# main.net
KiCad netlist of a schematic drawn in Altium Designer
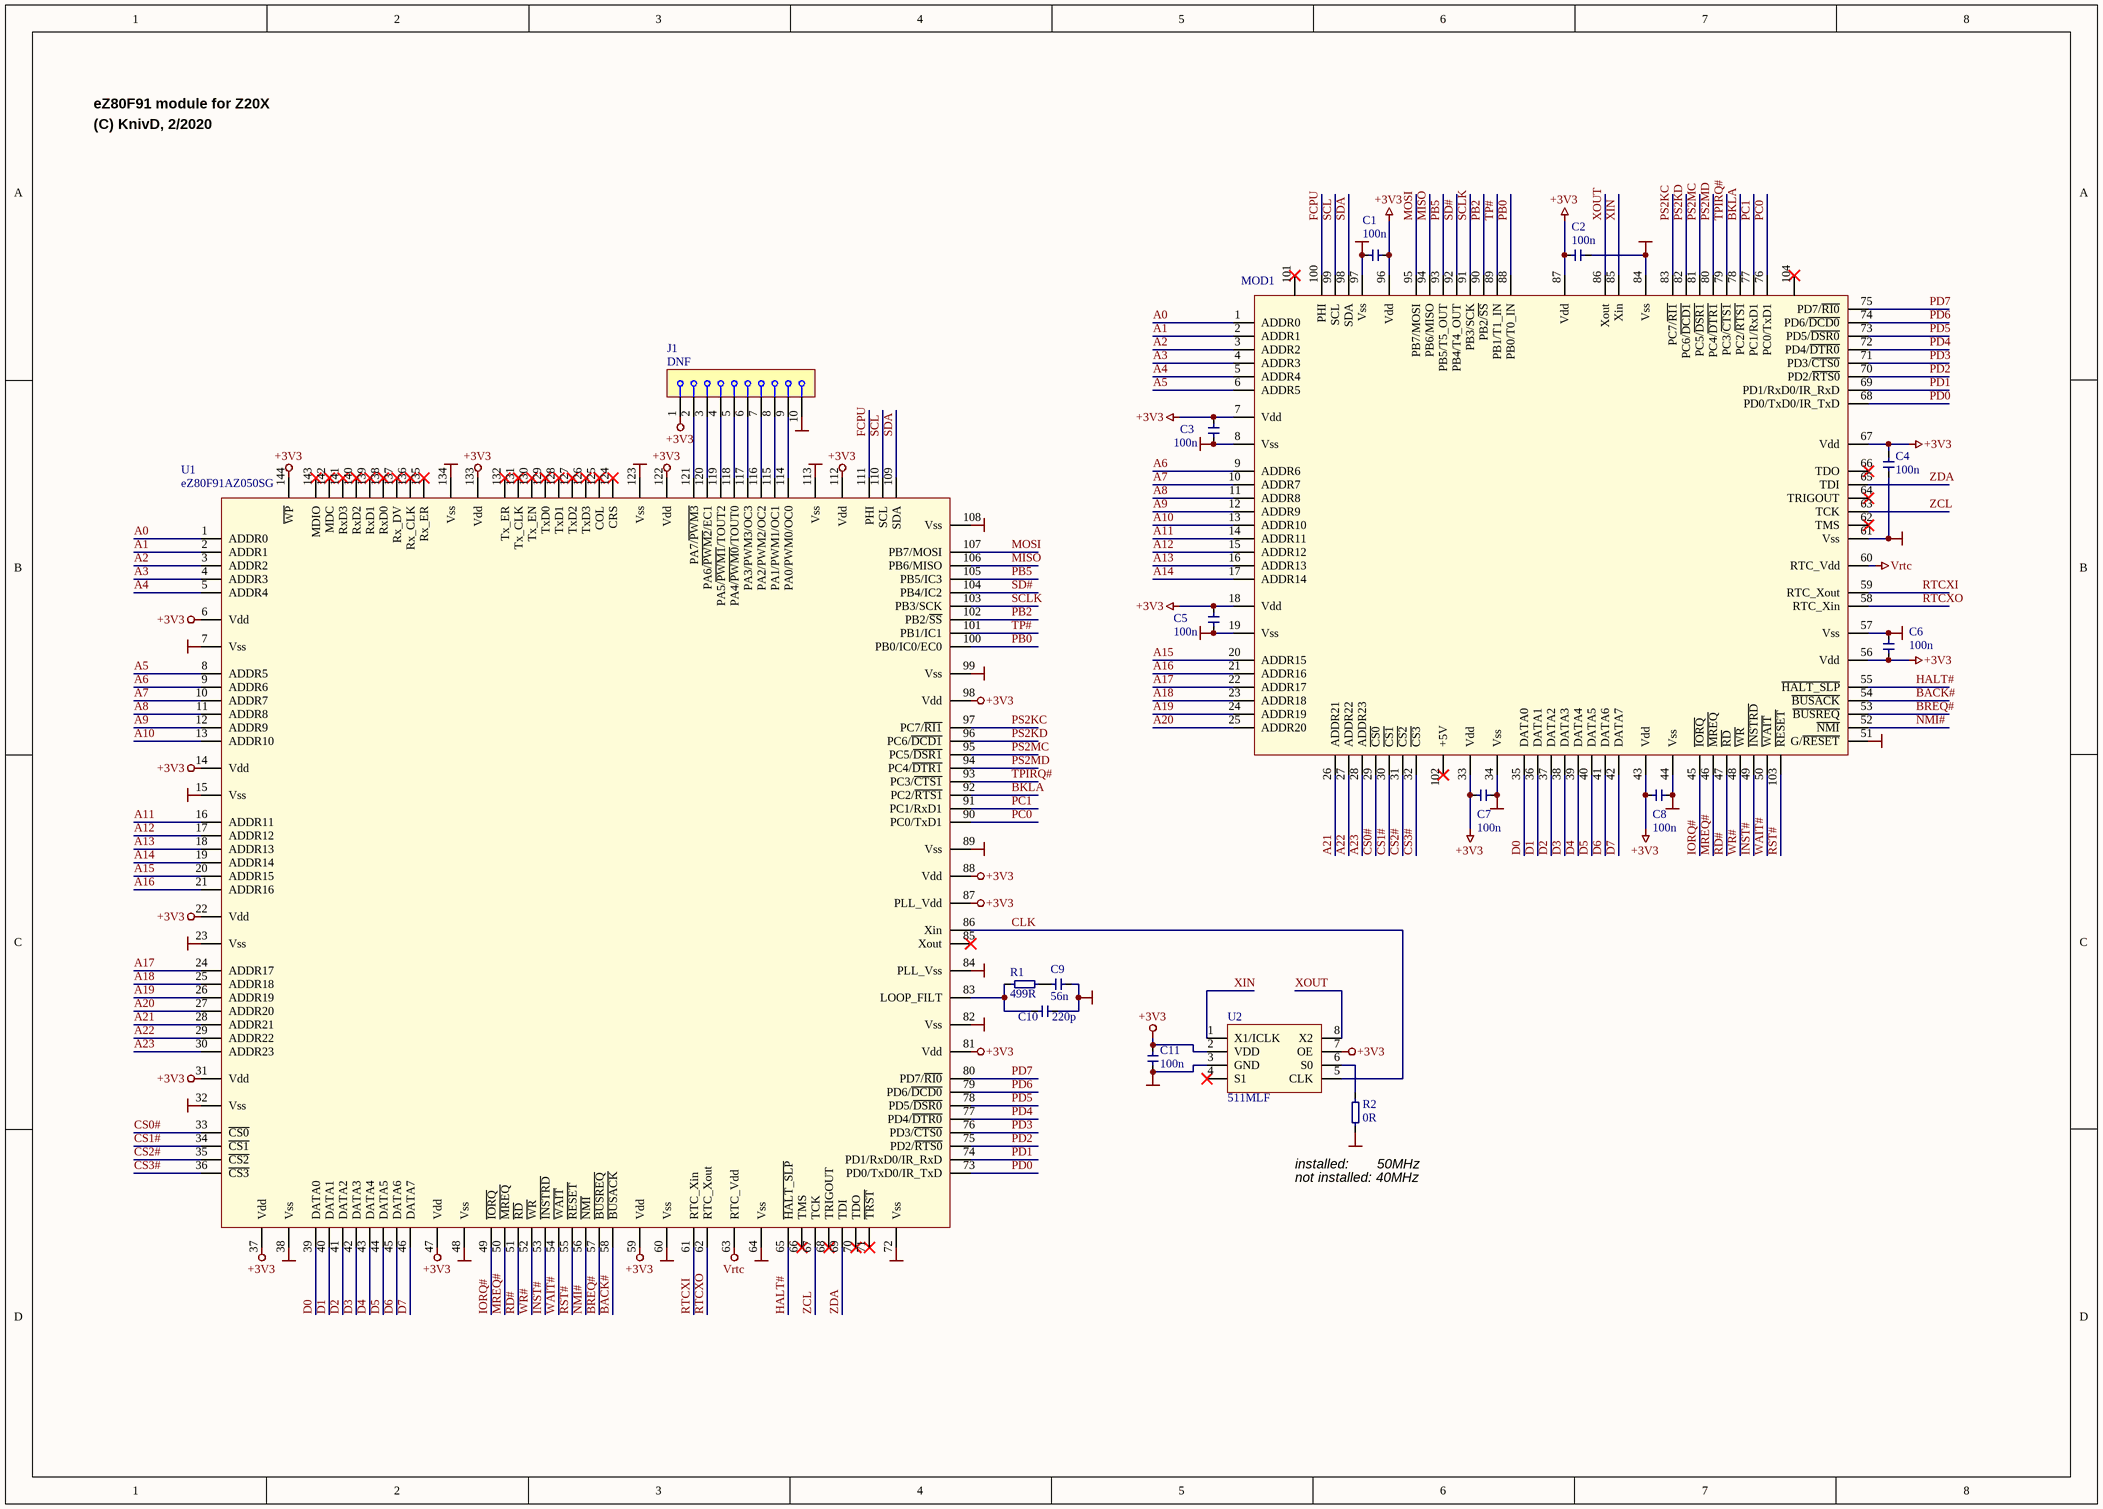
[diagram p0: main.SchDoc]

(export (version "E")
  (design (tool "Eeschema 10.0.6"))
  (components
    (comp (ref "C1")
      (value "100n")
      (footprint "_0805_CAP")
      (description "Capacitor")
      (libsource (lib "Discretes") (part "Capacitor"))
    )
    (comp (ref "C2")
      (value "100n")
      (footprint "_0805_CAP")
      (description "Capacitor")
      (libsource (lib "Discretes") (part "Capacitor"))
    )
    (comp (ref "C3")
      (value "100n")
      (footprint "_0805_CAP")
      (description "Capacitor")
      (libsource (lib "Discretes") (part "Capacitor"))
    )
    (comp (ref "C4")
      (value "100n")
      (footprint "_0805_CAP")
      (description "Capacitor")
      (libsource (lib "Discretes") (part "Capacitor"))
    )
    (comp (ref "C5")
      (value "100n")
      (footprint "_0805_CAP")
      (description "Capacitor")
      (libsource (lib "Discretes") (part "Capacitor"))
    )
    (comp (ref "C6")
      (value "100n")
      (footprint "_0805_CAP")
      (description "Capacitor")
      (libsource (lib "Discretes") (part "Capacitor"))
    )
    (comp (ref "C7")
      (value "100n")
      (footprint "_0805_CAP")
      (description "Capacitor")
      (libsource (lib "Discretes") (part "Capacitor"))
    )
    (comp (ref "C8")
      (value "100n")
      (footprint "_0805_CAP")
      (description "Capacitor")
      (libsource (lib "Discretes") (part "Capacitor"))
    )
    (comp (ref "C9")
      (value "56n")
      (footprint "_0805_CAP")
      (description "Capacitor")
      (libsource (lib "Discretes") (part "Capacitor"))
    )
    (comp (ref "C10")
      (value "220p")
      (footprint "_0805_CAP")
      (description "Capacitor")
      (libsource (lib "Discretes") (part "Capacitor"))
    )
    (comp (ref "C11")
      (value "100n")
      (footprint "_0805_CAP")
      (description "Capacitor")
      (libsource (lib "Discretes") (part "Capacitor"))
    )
    (comp (ref "J1")
      (value "DNF")
      (footprint "2011-1X10S")
      (description "Single row, 10-way connector")
      (libsource (lib "Connectors") (part "Connector 1x10"))
    )
    (comp (ref "MOD1")
      (value "Z20X CPU Module")
      (footprint "PGA100X15")
      (libsource (lib "Modules") (part "Z20X CPU Module"))
    )
    (comp (ref "R1")
      (value "499R")
      (footprint "_0805_RES")
      (description "Resistor")
      (libsource (lib "Discretes") (part "Resistor"))
    )
    (comp (ref "R2")
      (value "0R")
      (footprint "_0805_RES")
      (description "Resistor")
      (libsource (lib "") (part "Resistor_1"))
    )
    (comp (ref "U1")
      (value "eZ80F91AZ050SG")
      (footprint "QFP50P2200X2200X160-144N")
      (description "eZ80Acclaim!® Flash Microcontrollers")
      (fields (field (name "MANUFACTURER") "Zilog"))
      (libsource (lib "IC Microcontrollers and Processors") (part "eZ80F91"))
    )
    (comp (ref "U2")
      (value "511MLF")
      (footprint "SOIC8")
      (description "LOCO(tm) PLL CLOCK MULTIPLIER")
      (libsource (lib "IC Other Functions") (part "ICS511"))
    )
  )
  (nets
    (net (code "1") (name "+3V3") (class "Default")
      (node (ref "C1") (pin "1") (pintype "passive"))
      (node (ref "C11") (pin "2") (pintype "passive"))
      (node (ref "C2") (pin "2") (pintype "passive"))
      (node (ref "C3") (pin "1") (pintype "passive"))
      (node (ref "C4") (pin "2") (pintype "passive"))
      (node (ref "C5") (pin "1") (pintype "passive"))
      (node (ref "C6") (pin "1") (pintype "passive"))
      (node (ref "C7") (pin "1") (pintype "passive"))
      (node (ref "C8") (pin "1") (pintype "passive"))
      (node (ref "J1") (pin "1") (pinfunction "1_1") (pintype "passive"))
      (node (ref "MOD1") (pin "18") (pinfunction "Vdd_18") (pintype "passive"))
      (node (ref "MOD1") (pin "33") (pinfunction "Vdd_33") (pintype "passive"))
      (node (ref "MOD1") (pin "43") (pinfunction "Vdd_43") (pintype "passive"))
      (node (ref "MOD1") (pin "56") (pinfunction "Vdd_56") (pintype "passive"))
      (node (ref "MOD1") (pin "67") (pinfunction "Vdd_67") (pintype "passive"))
      (node (ref "MOD1") (pin "7") (pinfunction "Vdd_7") (pintype "passive"))
      (node (ref "MOD1") (pin "87") (pinfunction "Vdd_87") (pintype "passive"))
      (node (ref "MOD1") (pin "96") (pinfunction "Vdd_96") (pintype "passive"))
      (node (ref "U1") (pin "112") (pinfunction "Vdd_112") (pintype "passive"))
      (node (ref "U1") (pin "122") (pinfunction "Vdd_122") (pintype "passive"))
      (node (ref "U1") (pin "133") (pinfunction "Vdd_133") (pintype "passive"))
      (node (ref "U1") (pin "14") (pinfunction "Vdd_14") (pintype "passive"))
      (node (ref "U1") (pin "144") (pinfunction "~{WP}_144") (pintype "passive"))
      (node (ref "U1") (pin "22") (pinfunction "Vdd_22") (pintype "passive"))
      (node (ref "U1") (pin "31") (pinfunction "Vdd_31") (pintype "passive"))
      (node (ref "U1") (pin "37") (pinfunction "Vdd_37") (pintype "passive"))
      (node (ref "U1") (pin "47") (pinfunction "Vdd_47") (pintype "passive"))
      (node (ref "U1") (pin "59") (pinfunction "Vdd_59") (pintype "passive"))
      (node (ref "U1") (pin "6") (pinfunction "Vdd_6") (pintype "passive"))
      (node (ref "U1") (pin "81") (pinfunction "Vdd_81") (pintype "passive"))
      (node (ref "U1") (pin "87") (pinfunction "PLL_Vdd_87") (pintype "passive"))
      (node (ref "U1") (pin "88") (pinfunction "Vdd_88") (pintype "passive"))
      (node (ref "U1") (pin "98") (pinfunction "Vdd_98") (pintype "passive"))
      (node (ref "U2") (pin "2") (pinfunction "VDD_2") (pintype "passive"))
      (node (ref "U2") (pin "7") (pinfunction "OE_7") (pintype "passive"))
    )
    (net (code "2") (name "/A0") (class "Default")
      (node (ref "MOD1") (pin "1") (pinfunction "ADDR0_1") (pintype "passive"))
      (node (ref "U1") (pin "1") (pinfunction "ADDR0_1") (pintype "passive"))
    )
    (net (code "3") (name "/A1") (class "Default")
      (node (ref "MOD1") (pin "2") (pinfunction "ADDR1_2") (pintype "passive"))
      (node (ref "U1") (pin "2") (pinfunction "ADDR1_2") (pintype "passive"))
    )
    (net (code "4") (name "/A2") (class "Default")
      (node (ref "MOD1") (pin "3") (pinfunction "ADDR2_3") (pintype "passive"))
      (node (ref "U1") (pin "3") (pinfunction "ADDR2_3") (pintype "passive"))
    )
    (net (code "5") (name "/A3") (class "Default")
      (node (ref "MOD1") (pin "4") (pinfunction "ADDR3_4") (pintype "passive"))
      (node (ref "U1") (pin "4") (pinfunction "ADDR3_4") (pintype "passive"))
    )
    (net (code "6") (name "/A4") (class "Default")
      (node (ref "MOD1") (pin "5") (pinfunction "ADDR4_5") (pintype "passive"))
      (node (ref "U1") (pin "5") (pinfunction "ADDR4_5") (pintype "passive"))
    )
    (net (code "7") (name "/A5") (class "Default")
      (node (ref "MOD1") (pin "6") (pinfunction "ADDR5_6") (pintype "passive"))
      (node (ref "U1") (pin "8") (pinfunction "ADDR5_8") (pintype "passive"))
    )
    (net (code "8") (name "/A6") (class "Default")
      (node (ref "MOD1") (pin "9") (pinfunction "ADDR6_9") (pintype "passive"))
      (node (ref "U1") (pin "9") (pinfunction "ADDR6_9") (pintype "passive"))
    )
    (net (code "9") (name "/A7") (class "Default")
      (node (ref "MOD1") (pin "10") (pinfunction "ADDR7_10") (pintype "passive"))
      (node (ref "U1") (pin "10") (pinfunction "ADDR7_10") (pintype "passive"))
    )
    (net (code "10") (name "/A8") (class "Default")
      (node (ref "MOD1") (pin "11") (pinfunction "ADDR8_11") (pintype "passive"))
      (node (ref "U1") (pin "11") (pinfunction "ADDR8_11") (pintype "passive"))
    )
    (net (code "11") (name "/A9") (class "Default")
      (node (ref "MOD1") (pin "12") (pinfunction "ADDR9_12") (pintype "passive"))
      (node (ref "U1") (pin "12") (pinfunction "ADDR9_12") (pintype "passive"))
    )
    (net (code "12") (name "/A10") (class "Default")
      (node (ref "MOD1") (pin "13") (pinfunction "ADDR10_13") (pintype "passive"))
      (node (ref "U1") (pin "13") (pinfunction "ADDR10_13") (pintype "passive"))
    )
    (net (code "13") (name "/A11") (class "Default")
      (node (ref "MOD1") (pin "14") (pinfunction "ADDR11_14") (pintype "passive"))
      (node (ref "U1") (pin "16") (pinfunction "ADDR11_16") (pintype "passive"))
    )
    (net (code "14") (name "/A12") (class "Default")
      (node (ref "MOD1") (pin "15") (pinfunction "ADDR12_15") (pintype "passive"))
      (node (ref "U1") (pin "17") (pinfunction "ADDR12_17") (pintype "passive"))
    )
    (net (code "15") (name "/A13") (class "Default")
      (node (ref "MOD1") (pin "16") (pinfunction "ADDR13_16") (pintype "passive"))
      (node (ref "U1") (pin "18") (pinfunction "ADDR13_18") (pintype "passive"))
    )
    (net (code "16") (name "/A14") (class "Default")
      (node (ref "MOD1") (pin "17") (pinfunction "ADDR14_17") (pintype "passive"))
      (node (ref "U1") (pin "19") (pinfunction "ADDR14_19") (pintype "passive"))
    )
    (net (code "17") (name "/A15") (class "Default")
      (node (ref "MOD1") (pin "20") (pinfunction "ADDR15_20") (pintype "passive"))
      (node (ref "U1") (pin "20") (pinfunction "ADDR15_20") (pintype "passive"))
    )
    (net (code "18") (name "/A16") (class "Default")
      (node (ref "MOD1") (pin "21") (pinfunction "ADDR16_21") (pintype "passive"))
      (node (ref "U1") (pin "21") (pinfunction "ADDR16_21") (pintype "passive"))
    )
    (net (code "19") (name "/A17") (class "Default")
      (node (ref "MOD1") (pin "22") (pinfunction "ADDR17_22") (pintype "passive"))
      (node (ref "U1") (pin "24") (pinfunction "ADDR17_24") (pintype "passive"))
    )
    (net (code "20") (name "/A18") (class "Default")
      (node (ref "MOD1") (pin "23") (pinfunction "ADDR18_23") (pintype "passive"))
      (node (ref "U1") (pin "25") (pinfunction "ADDR18_25") (pintype "passive"))
    )
    (net (code "21") (name "/A19") (class "Default")
      (node (ref "MOD1") (pin "24") (pinfunction "ADDR19_24") (pintype "passive"))
      (node (ref "U1") (pin "26") (pinfunction "ADDR19_26") (pintype "passive"))
    )
    (net (code "22") (name "/A20") (class "Default")
      (node (ref "MOD1") (pin "25") (pinfunction "ADDR20_25") (pintype "passive"))
      (node (ref "U1") (pin "27") (pinfunction "ADDR20_27") (pintype "passive"))
    )
    (net (code "23") (name "/A21") (class "Default")
      (node (ref "MOD1") (pin "26") (pinfunction "ADDR21_26") (pintype "passive"))
      (node (ref "U1") (pin "28") (pinfunction "ADDR21_28") (pintype "passive"))
    )
    (net (code "24") (name "/A22") (class "Default")
      (node (ref "MOD1") (pin "27") (pinfunction "ADDR22_27") (pintype "passive"))
      (node (ref "U1") (pin "29") (pinfunction "ADDR22_29") (pintype "passive"))
    )
    (net (code "25") (name "/A23") (class "Default")
      (node (ref "MOD1") (pin "28") (pinfunction "ADDR23_28") (pintype "passive"))
      (node (ref "U1") (pin "30") (pinfunction "ADDR23_30") (pintype "passive"))
    )
    (net (code "26") (name "/BACK#") (class "Default")
      (node (ref "MOD1") (pin "54") (pinfunction "~{BUSACK}_54") (pintype "passive"))
      (node (ref "U1") (pin "58") (pinfunction "~{BUSACK}_58") (pintype "passive"))
    )
    (net (code "27") (name "/BKLA") (class "Default")
      (node (ref "MOD1") (pin "78") (pinfunction "PC2/~{RTS1}_78") (pintype "passive"))
      (node (ref "U1") (pin "92") (pinfunction "PC2/~{RTS1}_92") (pintype "passive"))
    )
    (net (code "28") (name "/BREQ#") (class "Default")
      (node (ref "MOD1") (pin "53") (pinfunction "~{BUSREQ}_53") (pintype "passive"))
      (node (ref "U1") (pin "57") (pinfunction "~{BUSREQ}_57") (pintype "passive"))
    )
    (net (code "29") (name "/CLK") (class "Default")
      (node (ref "U1") (pin "86") (pinfunction "Xin_86") (pintype "passive"))
      (node (ref "U2") (pin "5") (pinfunction "CLK_5") (pintype "passive"))
    )
    (net (code "30") (name "/CS0#") (class "Default")
      (node (ref "MOD1") (pin "29") (pinfunction "~{CS0}_29") (pintype "passive"))
      (node (ref "U1") (pin "33") (pinfunction "~{CS0}_33") (pintype "passive"))
    )
    (net (code "31") (name "/CS1#") (class "Default")
      (node (ref "MOD1") (pin "30") (pinfunction "~{CS1}_30") (pintype "passive"))
      (node (ref "U1") (pin "34") (pinfunction "~{CS1}_34") (pintype "passive"))
    )
    (net (code "32") (name "/CS2#") (class "Default")
      (node (ref "MOD1") (pin "31") (pinfunction "~{CS2}_31") (pintype "passive"))
      (node (ref "U1") (pin "35") (pinfunction "~{CS2}_35") (pintype "passive"))
    )
    (net (code "33") (name "/CS3#") (class "Default")
      (node (ref "MOD1") (pin "32") (pinfunction "~{CS3}_32") (pintype "passive"))
      (node (ref "U1") (pin "36") (pinfunction "~{CS3}_36") (pintype "passive"))
    )
    (net (code "34") (name "/D0") (class "Default")
      (node (ref "MOD1") (pin "35") (pinfunction "DATA0_35") (pintype "passive"))
      (node (ref "U1") (pin "39") (pinfunction "DATA0_39") (pintype "passive"))
    )
    (net (code "35") (name "/D1") (class "Default")
      (node (ref "MOD1") (pin "36") (pinfunction "DATA1_36") (pintype "passive"))
      (node (ref "U1") (pin "40") (pinfunction "DATA1_40") (pintype "passive"))
    )
    (net (code "36") (name "/D2") (class "Default")
      (node (ref "MOD1") (pin "37") (pinfunction "DATA2_37") (pintype "passive"))
      (node (ref "U1") (pin "41") (pinfunction "DATA2_41") (pintype "passive"))
    )
    (net (code "37") (name "/D3") (class "Default")
      (node (ref "MOD1") (pin "38") (pinfunction "DATA3_38") (pintype "passive"))
      (node (ref "U1") (pin "42") (pinfunction "DATA3_42") (pintype "passive"))
    )
    (net (code "38") (name "/D4") (class "Default")
      (node (ref "MOD1") (pin "39") (pinfunction "DATA4_39") (pintype "passive"))
      (node (ref "U1") (pin "43") (pinfunction "DATA4_43") (pintype "passive"))
    )
    (net (code "39") (name "/D5") (class "Default")
      (node (ref "MOD1") (pin "40") (pinfunction "DATA5_40") (pintype "passive"))
      (node (ref "U1") (pin "44") (pinfunction "DATA5_44") (pintype "passive"))
    )
    (net (code "40") (name "/D6") (class "Default")
      (node (ref "MOD1") (pin "41") (pinfunction "DATA6_41") (pintype "passive"))
      (node (ref "U1") (pin "45") (pinfunction "DATA6_45") (pintype "passive"))
    )
    (net (code "41") (name "/D7") (class "Default")
      (node (ref "MOD1") (pin "42") (pinfunction "DATA7_42") (pintype "passive"))
      (node (ref "U1") (pin "46") (pinfunction "DATA7_46") (pintype "passive"))
    )
    (net (code "42") (name "/FCPU") (class "Default")
      (node (ref "MOD1") (pin "100") (pinfunction "PHI_100") (pintype "passive"))
      (node (ref "U1") (pin "111") (pinfunction "PHI_111") (pintype "passive"))
    )
    (net (code "43") (name "/HALT#") (class "Default")
      (node (ref "MOD1") (pin "55") (pinfunction "~{HALT_SLP}_55") (pintype "passive"))
      (node (ref "U1") (pin "65") (pinfunction "~{HALT_SLP}_65") (pintype "passive"))
    )
    (net (code "44") (name "/INST#") (class "Default")
      (node (ref "MOD1") (pin "49") (pinfunction "~{INSTRD}_49") (pintype "passive"))
      (node (ref "U1") (pin "53") (pinfunction "~{INSTRD}_53") (pintype "passive"))
    )
    (net (code "45") (name "/IORQ#") (class "Default")
      (node (ref "MOD1") (pin "45") (pinfunction "~{IORQ}_45") (pintype "passive"))
      (node (ref "U1") (pin "49") (pinfunction "~{IORQ}_49") (pintype "passive"))
    )
    (net (code "46") (name "/MISO") (class "Default")
      (node (ref "MOD1") (pin "94") (pinfunction "PB6/MISO_94") (pintype "passive"))
      (node (ref "U1") (pin "106") (pinfunction "PB6/MISO_106") (pintype "passive"))
    )
    (net (code "47") (name "/MOSI") (class "Default")
      (node (ref "MOD1") (pin "95") (pinfunction "PB7/MOSI_95") (pintype "passive"))
      (node (ref "U1") (pin "107") (pinfunction "PB7/MOSI_107") (pintype "passive"))
    )
    (net (code "48") (name "/MREQ#") (class "Default")
      (node (ref "MOD1") (pin "46") (pinfunction "~{MREQ}_46") (pintype "passive"))
      (node (ref "U1") (pin "50") (pinfunction "~{MREQ}_50") (pintype "passive"))
    )
    (net (code "49") (name "/NMI#") (class "Default")
      (node (ref "MOD1") (pin "52") (pinfunction "~{NMI}_52") (pintype "passive"))
      (node (ref "U1") (pin "56") (pinfunction "~{NMI}_56") (pintype "passive"))
    )
    (net (code "50") (name "/PB0") (class "Default")
      (node (ref "MOD1") (pin "88") (pinfunction "PB0/T0_IN_88") (pintype "passive"))
      (node (ref "U1") (pin "100") (pinfunction "PB0/IC0/EC0_100") (pintype "passive"))
    )
    (net (code "51") (name "/PB2") (class "Default")
      (node (ref "MOD1") (pin "90") (pinfunction "PB2/~{SS}_90") (pintype "passive"))
      (node (ref "U1") (pin "102") (pinfunction "PB2/~{SS}_102") (pintype "passive"))
    )
    (net (code "52") (name "/PB5") (class "Default")
      (node (ref "MOD1") (pin "93") (pinfunction "PB5/T5_OUT_93") (pintype "passive"))
      (node (ref "U1") (pin "105") (pinfunction "PB5/IC3_105") (pintype "passive"))
    )
    (net (code "53") (name "/PC0") (class "Default")
      (node (ref "MOD1") (pin "76") (pinfunction "PC0/TxD1_76") (pintype "passive"))
      (node (ref "U1") (pin "90") (pinfunction "PC0/TxD1_90") (pintype "passive"))
    )
    (net (code "54") (name "/PC1") (class "Default")
      (node (ref "MOD1") (pin "77") (pinfunction "PC1/RxD1_77") (pintype "passive"))
      (node (ref "U1") (pin "91") (pinfunction "PC1/RxD1_91") (pintype "passive"))
    )
    (net (code "55") (name "/PD0") (class "Default")
      (node (ref "MOD1") (pin "68") (pinfunction "PD0/TxD0/IR_TxD_68") (pintype "passive"))
      (node (ref "U1") (pin "73") (pinfunction "PD0/TxD0/IR_TxD_73") (pintype "passive"))
    )
    (net (code "56") (name "/PD1") (class "Default")
      (node (ref "MOD1") (pin "69") (pinfunction "PD1/RxD0/IR_RxD_69") (pintype "passive"))
      (node (ref "U1") (pin "74") (pinfunction "PD1/RxD0/IR_RxD_74") (pintype "passive"))
    )
    (net (code "57") (name "/PD2") (class "Default")
      (node (ref "MOD1") (pin "70") (pinfunction "PD2/~{RTS0}_70") (pintype "passive"))
      (node (ref "U1") (pin "75") (pinfunction "PD2/~{RTS0}_75") (pintype "passive"))
    )
    (net (code "58") (name "/PD3") (class "Default")
      (node (ref "MOD1") (pin "71") (pinfunction "PD3/~{CTS0}_71") (pintype "passive"))
      (node (ref "U1") (pin "76") (pinfunction "PD3/~{CTS0}_76") (pintype "passive"))
    )
    (net (code "59") (name "/PD4") (class "Default")
      (node (ref "MOD1") (pin "72") (pinfunction "PD4/~{DTR0}_72") (pintype "passive"))
      (node (ref "U1") (pin "77") (pinfunction "PD4/~{DTR0}_77") (pintype "passive"))
    )
    (net (code "60") (name "/PD5") (class "Default")
      (node (ref "MOD1") (pin "73") (pinfunction "PD5/~{DSR0}_73") (pintype "passive"))
      (node (ref "U1") (pin "78") (pinfunction "PD5/~{DSR0}_78") (pintype "passive"))
    )
    (net (code "61") (name "/PD6") (class "Default")
      (node (ref "MOD1") (pin "74") (pinfunction "PD6/~{DCD0}_74") (pintype "passive"))
      (node (ref "U1") (pin "79") (pinfunction "PD6/~{DCD0}_79") (pintype "passive"))
    )
    (net (code "62") (name "/PD7") (class "Default")
      (node (ref "MOD1") (pin "75") (pinfunction "PD7/~{RI0}_75") (pintype "passive"))
      (node (ref "U1") (pin "80") (pinfunction "PD7/~{RI0}_80") (pintype "passive"))
    )
    (net (code "63") (name "/PS2KC") (class "Default")
      (node (ref "MOD1") (pin "83") (pinfunction "PC7/~{RI1}_83") (pintype "passive"))
      (node (ref "U1") (pin "97") (pinfunction "PC7/~{RI1}_97") (pintype "passive"))
    )
    (net (code "64") (name "/PS2KD") (class "Default")
      (node (ref "MOD1") (pin "82") (pinfunction "PC6/~{DCD1}_82") (pintype "passive"))
      (node (ref "U1") (pin "96") (pinfunction "PC6/~{DCD1}_96") (pintype "passive"))
    )
    (net (code "65") (name "/PS2MC") (class "Default")
      (node (ref "MOD1") (pin "81") (pinfunction "PC5/~{DSR1}_81") (pintype "passive"))
      (node (ref "U1") (pin "95") (pinfunction "PC5/~{DSR1}_95") (pintype "passive"))
    )
    (net (code "66") (name "/PS2MD") (class "Default")
      (node (ref "MOD1") (pin "80") (pinfunction "PC4/~{DTR1}_80") (pintype "passive"))
      (node (ref "U1") (pin "94") (pinfunction "PC4/~{DTR1}_94") (pintype "passive"))
    )
    (net (code "67") (name "/RD#") (class "Default")
      (node (ref "MOD1") (pin "47") (pinfunction "~{RD}_47") (pintype "passive"))
      (node (ref "U1") (pin "51") (pinfunction "~{RD}_51") (pintype "passive"))
    )
    (net (code "68") (name "/RST#") (class "Default")
      (node (ref "MOD1") (pin "103") (pinfunction "~{RESET}_103") (pintype "passive"))
      (node (ref "U1") (pin "55") (pinfunction "~{RESET}_55") (pintype "passive"))
    )
    (net (code "69") (name "/RTCXI") (class "Default")
      (node (ref "MOD1") (pin "59") (pinfunction "RTC_Xout_59") (pintype "passive"))
      (node (ref "U1") (pin "61") (pinfunction "RTC_Xin_61") (pintype "passive"))
    )
    (net (code "70") (name "/RTCXO") (class "Default")
      (node (ref "MOD1") (pin "58") (pinfunction "RTC_Xin_58") (pintype "passive"))
      (node (ref "U1") (pin "62") (pinfunction "RTC_Xout_62") (pintype "passive"))
    )
    (net (code "71") (name "/SCL") (class "Default")
      (node (ref "MOD1") (pin "99") (pinfunction "SCL_99") (pintype "passive"))
      (node (ref "U1") (pin "110") (pinfunction "SCL_110") (pintype "passive"))
    )
    (net (code "72") (name "/SCLK") (class "Default")
      (node (ref "MOD1") (pin "91") (pinfunction "PB3/SCK_91") (pintype "passive"))
      (node (ref "U1") (pin "103") (pinfunction "PB3/SCK_103") (pintype "passive"))
    )
    (net (code "73") (name "/SD#") (class "Default")
      (node (ref "MOD1") (pin "92") (pinfunction "PB4/T4_OUT_92") (pintype "passive"))
      (node (ref "U1") (pin "104") (pinfunction "PB4/IC2_104") (pintype "passive"))
    )
    (net (code "74") (name "/SDA") (class "Default")
      (node (ref "MOD1") (pin "98") (pinfunction "SDA_98") (pintype "passive"))
      (node (ref "U1") (pin "109") (pinfunction "SDA_109") (pintype "passive"))
    )
    (net (code "75") (name "/TP#") (class "Default")
      (node (ref "MOD1") (pin "89") (pinfunction "PB1/T1_IN_89") (pintype "passive"))
      (node (ref "U1") (pin "101") (pinfunction "PB1/IC1_101") (pintype "passive"))
    )
    (net (code "76") (name "/TPIRQ#") (class "Default")
      (node (ref "MOD1") (pin "79") (pinfunction "PC3/~{CTS1}_79") (pintype "passive"))
      (node (ref "U1") (pin "93") (pinfunction "PC3/~{CTS1}_93") (pintype "passive"))
    )
    (net (code "77") (name "/WAIT#") (class "Default")
      (node (ref "MOD1") (pin "50") (pinfunction "~{WAIT}_50") (pintype "passive"))
      (node (ref "U1") (pin "54") (pinfunction "~{WAIT}_54") (pintype "passive"))
    )
    (net (code "78") (name "/WR#") (class "Default")
      (node (ref "MOD1") (pin "48") (pinfunction "~{WR}_48") (pintype "passive"))
      (node (ref "U1") (pin "52") (pinfunction "~{WR}_52") (pintype "passive"))
    )
    (net (code "79") (name "/XIN") (class "Default")
      (node (ref "MOD1") (pin "85") (pinfunction "Xin_85") (pintype "passive"))
      (node (ref "U2") (pin "1") (pinfunction "X1/ICLK_1") (pintype "passive"))
    )
    (net (code "80") (name "/XOUT") (class "Default")
      (node (ref "MOD1") (pin "86") (pinfunction "Xout_86") (pintype "passive"))
      (node (ref "U2") (pin "8") (pinfunction "X2_8") (pintype "passive"))
    )
    (net (code "81") (name "/ZCL") (class "Default")
      (node (ref "MOD1") (pin "63") (pinfunction "TCK_63") (pintype "passive"))
      (node (ref "U1") (pin "67") (pinfunction "TCK_67") (pintype "passive"))
    )
    (net (code "82") (name "/ZDA") (class "Default")
      (node (ref "MOD1") (pin "65") (pinfunction "TDI_65") (pintype "passive"))
      (node (ref "U1") (pin "69") (pinfunction "TDI_69") (pintype "passive"))
    )
    (net (code "83") (name "GND") (class "Default")
      (node (ref "C1") (pin "2") (pintype "passive"))
      (node (ref "C10") (pin "2") (pintype "passive"))
      (node (ref "C11") (pin "1") (pintype "passive"))
      (node (ref "C2") (pin "1") (pintype "passive"))
      (node (ref "C3") (pin "2") (pintype "passive"))
      (node (ref "C4") (pin "1") (pintype "passive"))
      (node (ref "C5") (pin "2") (pintype "passive"))
      (node (ref "C6") (pin "2") (pintype "passive"))
      (node (ref "C7") (pin "2") (pintype "passive"))
      (node (ref "C8") (pin "2") (pintype "passive"))
      (node (ref "C9") (pin "2") (pintype "passive"))
      (node (ref "J1") (pin "10") (pinfunction "10_10") (pintype "passive"))
      (node (ref "MOD1") (pin "19") (pinfunction "Vss_19") (pintype "passive"))
      (node (ref "MOD1") (pin "34") (pinfunction "Vss_34") (pintype "passive"))
      (node (ref "MOD1") (pin "44") (pinfunction "Vss_44") (pintype "passive"))
      (node (ref "MOD1") (pin "51") (pinfunction "G/~{RESET}_51") (pintype "passive"))
      (node (ref "MOD1") (pin "57") (pinfunction "Vss_57") (pintype "passive"))
      (node (ref "MOD1") (pin "61") (pinfunction "Vss_61") (pintype "passive"))
      (node (ref "MOD1") (pin "8") (pinfunction "Vss_8") (pintype "passive"))
      (node (ref "MOD1") (pin "84") (pinfunction "Vss_84") (pintype "passive"))
      (node (ref "MOD1") (pin "97") (pinfunction "Vss_97") (pintype "passive"))
      (node (ref "R2") (pin "1") (pintype "passive"))
      (node (ref "U1") (pin "108") (pinfunction "Vss_108") (pintype "passive"))
      (node (ref "U1") (pin "113") (pinfunction "Vss_113") (pintype "passive"))
      (node (ref "U1") (pin "123") (pinfunction "Vss_123") (pintype "passive"))
      (node (ref "U1") (pin "134") (pinfunction "Vss_134") (pintype "passive"))
      (node (ref "U1") (pin "15") (pinfunction "Vss_15") (pintype "passive"))
      (node (ref "U1") (pin "23") (pinfunction "Vss_23") (pintype "passive"))
      (node (ref "U1") (pin "32") (pinfunction "Vss_32") (pintype "passive"))
      (node (ref "U1") (pin "38") (pinfunction "Vss_38") (pintype "passive"))
      (node (ref "U1") (pin "48") (pinfunction "Vss_48") (pintype "passive"))
      (node (ref "U1") (pin "60") (pinfunction "Vss_60") (pintype "passive"))
      (node (ref "U1") (pin "64") (pinfunction "Vss_64") (pintype "passive"))
      (node (ref "U1") (pin "7") (pinfunction "Vss_7") (pintype "passive"))
      (node (ref "U1") (pin "72") (pinfunction "Vss_72") (pintype "passive"))
      (node (ref "U1") (pin "82") (pinfunction "Vss_82") (pintype "passive"))
      (node (ref "U1") (pin "84") (pinfunction "PLL_Vss_84") (pintype "passive"))
      (node (ref "U1") (pin "89") (pinfunction "Vss_89") (pintype "passive"))
      (node (ref "U1") (pin "99") (pinfunction "Vss_99") (pintype "passive"))
      (node (ref "U2") (pin "3") (pinfunction "GND_3") (pintype "passive"))
    )
    (net (code "84") (name "Net-(C9-Pad1)") (class "Default")
      (node (ref "C9") (pin "1") (pintype "passive"))
      (node (ref "R1") (pin "2") (pintype "passive"))
    )
    (net (code "85") (name "Net-(U1-LOOP_FILT)") (class "Default")
      (node (ref "C10") (pin "1") (pintype "passive"))
      (node (ref "R1") (pin "1") (pintype "passive"))
      (node (ref "U1") (pin "83") (pinfunction "LOOP_FILT_83") (pintype "passive"))
    )
    (net (code "86") (name "Net-(U1-PA0{slash}PWM0{slash}OC0)") (class "Default")
      (node (ref "J1") (pin "9") (pinfunction "9_9") (pintype "passive"))
      (node (ref "U1") (pin "114") (pinfunction "PA0/PWM0/OC0_114") (pintype "passive"))
    )
    (net (code "87") (name "Net-(U1-PA1{slash}PWM1{slash}OC1)") (class "Default")
      (node (ref "J1") (pin "8") (pinfunction "8_8") (pintype "passive"))
      (node (ref "U1") (pin "115") (pinfunction "PA1/PWM1/OC1_115") (pintype "passive"))
    )
    (net (code "88") (name "Net-(U1-PA2{slash}PWM2{slash}OC2)") (class "Default")
      (node (ref "J1") (pin "7") (pinfunction "7_7") (pintype "passive"))
      (node (ref "U1") (pin "116") (pinfunction "PA2/PWM2/OC2_116") (pintype "passive"))
    )
    (net (code "89") (name "Net-(U1-PA3{slash}PWM3{slash}OC3)") (class "Default")
      (node (ref "J1") (pin "6") (pinfunction "6_6") (pintype "passive"))
      (node (ref "U1") (pin "117") (pinfunction "PA3/PWM3/OC3_117") (pintype "passive"))
    )
    (net (code "90") (name "Net-(U1-PA4{slash}~{PWM0}{slash}TOUT0)") (class "Default")
      (node (ref "J1") (pin "5") (pinfunction "5_5") (pintype "passive"))
      (node (ref "U1") (pin "118") (pinfunction "PA4/~{PWM0}/TOUT0_118") (pintype "passive"))
    )
    (net (code "91") (name "Net-(U1-PA5{slash}~{PWM1}{slash}TOUT2)") (class "Default")
      (node (ref "J1") (pin "4") (pinfunction "4_4") (pintype "passive"))
      (node (ref "U1") (pin "119") (pinfunction "PA5/~{PWM1}/TOUT2_119") (pintype "passive"))
    )
    (net (code "92") (name "Net-(U1-PA6{slash}~{PWM2}{slash}EC1)") (class "Default")
      (node (ref "J1") (pin "3") (pinfunction "3_3") (pintype "passive"))
      (node (ref "U1") (pin "120") (pinfunction "PA6/~{PWM2}/EC1_120") (pintype "passive"))
    )
    (net (code "93") (name "Net-(U1-PA7{slash}~{PWM3})") (class "Default")
      (node (ref "J1") (pin "2") (pinfunction "2_2") (pintype "passive"))
      (node (ref "U1") (pin "121") (pinfunction "PA7/~{PWM3}_121") (pintype "passive"))
    )
    (net (code "94") (name "Net-(U2-S0)") (class "Default")
      (node (ref "R2") (pin "2") (pintype "passive"))
      (node (ref "U2") (pin "6") (pinfunction "S0_6") (pintype "passive"))
    )
    (net (code "95") (name "Vrtc") (class "Default")
      (node (ref "MOD1") (pin "60") (pinfunction "RTC_Vdd_60") (pintype "passive"))
      (node (ref "U1") (pin "63") (pinfunction "RTC_Vdd_63") (pintype "passive"))
    )
    (net (code "96") (name "unconnected-(MOD1-+5V-Pad102)") (class "Default")
      (node (ref "MOD1") (pin "102") (pinfunction "+5V_102") (pintype "passive+no_connect"))
    )
    (net (code "97") (name "unconnected-(MOD1-Pad101)") (class "Default")
      (node (ref "MOD1") (pin "101") (pintype "passive+no_connect"))
    )
    (net (code "98") (name "unconnected-(MOD1-Pad104)") (class "Default")
      (node (ref "MOD1") (pin "104") (pintype "passive+no_connect"))
    )
    (net (code "99") (name "unconnected-(MOD1-TDO-Pad66)") (class "Default")
      (node (ref "MOD1") (pin "66") (pinfunction "TDO_66") (pintype "passive+no_connect"))
    )
    (net (code "100") (name "unconnected-(MOD1-TMS-Pad62)") (class "Default")
      (node (ref "MOD1") (pin "62") (pinfunction "TMS_62") (pintype "passive+no_connect"))
    )
    (net (code "101") (name "unconnected-(MOD1-TRIGOUT-Pad64)") (class "Default")
      (node (ref "MOD1") (pin "64") (pinfunction "TRIGOUT_64") (pintype "passive+no_connect"))
    )
    (net (code "102") (name "unconnected-(U1-COL-Pad125)") (class "Default")
      (node (ref "U1") (pin "125") (pinfunction "COL_125") (pintype "passive+no_connect"))
    )
    (net (code "103") (name "unconnected-(U1-CRS-Pad124)") (class "Default")
      (node (ref "U1") (pin "124") (pinfunction "CRS_124") (pintype "passive+no_connect"))
    )
    (net (code "104") (name "unconnected-(U1-MDC-Pad142)") (class "Default")
      (node (ref "U1") (pin "142") (pinfunction "MDC_142") (pintype "passive+no_connect"))
    )
    (net (code "105") (name "unconnected-(U1-MDIO-Pad143)") (class "Default")
      (node (ref "U1") (pin "143") (pinfunction "MDIO_143") (pintype "passive+no_connect"))
    )
    (net (code "106") (name "unconnected-(U1-RxD0-Pad138)") (class "Default")
      (node (ref "U1") (pin "138") (pinfunction "RxD0_138") (pintype "passive+no_connect"))
    )
    (net (code "107") (name "unconnected-(U1-RxD1-Pad139)") (class "Default")
      (node (ref "U1") (pin "139") (pinfunction "RxD1_139") (pintype "passive+no_connect"))
    )
    (net (code "108") (name "unconnected-(U1-RxD2-Pad140)") (class "Default")
      (node (ref "U1") (pin "140") (pinfunction "RxD2_140") (pintype "passive+no_connect"))
    )
    (net (code "109") (name "unconnected-(U1-RxD3-Pad141)") (class "Default")
      (node (ref "U1") (pin "141") (pinfunction "RxD3_141") (pintype "passive+no_connect"))
    )
    (net (code "110") (name "unconnected-(U1-Rx_CLK-Pad136)") (class "Default")
      (node (ref "U1") (pin "136") (pinfunction "Rx_CLK_136") (pintype "passive+no_connect"))
    )
    (net (code "111") (name "unconnected-(U1-Rx_DV-Pad137)") (class "Default")
      (node (ref "U1") (pin "137") (pinfunction "Rx_DV_137") (pintype "passive+no_connect"))
    )
    (net (code "112") (name "unconnected-(U1-Rx_ER-Pad135)") (class "Default")
      (node (ref "U1") (pin "135") (pinfunction "Rx_ER_135") (pintype "passive+no_connect"))
    )
    (net (code "113") (name "unconnected-(U1-TDO-Pad70)") (class "Default")
      (node (ref "U1") (pin "70") (pinfunction "TDO_70") (pintype "passive+no_connect"))
    )
    (net (code "114") (name "unconnected-(U1-TMS-Pad66)") (class "Default")
      (node (ref "U1") (pin "66") (pinfunction "TMS_66") (pintype "passive+no_connect"))
    )
    (net (code "115") (name "unconnected-(U1-TRIGOUT-Pad68)") (class "Default")
      (node (ref "U1") (pin "68") (pinfunction "TRIGOUT_68") (pintype "passive+no_connect"))
    )
    (net (code "116") (name "unconnected-(U1-TxD0-Pad129)") (class "Default")
      (node (ref "U1") (pin "129") (pinfunction "TxD0_129") (pintype "passive+no_connect"))
    )
    (net (code "117") (name "unconnected-(U1-TxD1-Pad128)") (class "Default")
      (node (ref "U1") (pin "128") (pinfunction "TxD1_128") (pintype "passive+no_connect"))
    )
    (net (code "118") (name "unconnected-(U1-TxD2-Pad127)") (class "Default")
      (node (ref "U1") (pin "127") (pinfunction "TxD2_127") (pintype "passive+no_connect"))
    )
    (net (code "119") (name "unconnected-(U1-TxD3-Pad126)") (class "Default")
      (node (ref "U1") (pin "126") (pinfunction "TxD3_126") (pintype "passive+no_connect"))
    )
    (net (code "120") (name "unconnected-(U1-Tx_CLK-Pad131)") (class "Default")
      (node (ref "U1") (pin "131") (pinfunction "Tx_CLK_131") (pintype "passive+no_connect"))
    )
    (net (code "121") (name "unconnected-(U1-Tx_EN-Pad130)") (class "Default")
      (node (ref "U1") (pin "130") (pinfunction "Tx_EN_130") (pintype "passive+no_connect"))
    )
    (net (code "122") (name "unconnected-(U1-Tx_ER-Pad132)") (class "Default")
      (node (ref "U1") (pin "132") (pinfunction "Tx_ER_132") (pintype "passive+no_connect"))
    )
    (net (code "123") (name "unconnected-(U1-Xout-Pad85)") (class "Default")
      (node (ref "U1") (pin "85") (pinfunction "Xout_85") (pintype "passive+no_connect"))
    )
    (net (code "124") (name "unconnected-(U1-~{TRST}-Pad71)") (class "Default")
      (node (ref "U1") (pin "71") (pinfunction "~{TRST}_71") (pintype "passive+no_connect"))
    )
    (net (code "125") (name "unconnected-(U2-S1-Pad4)") (class "Default")
      (node (ref "U2") (pin "4") (pinfunction "S1_4") (pintype "passive+no_connect"))
    )
  )
)
